# STM32F401RCT6.net
KiCad netlist of a schematic drawn in Altium Designer
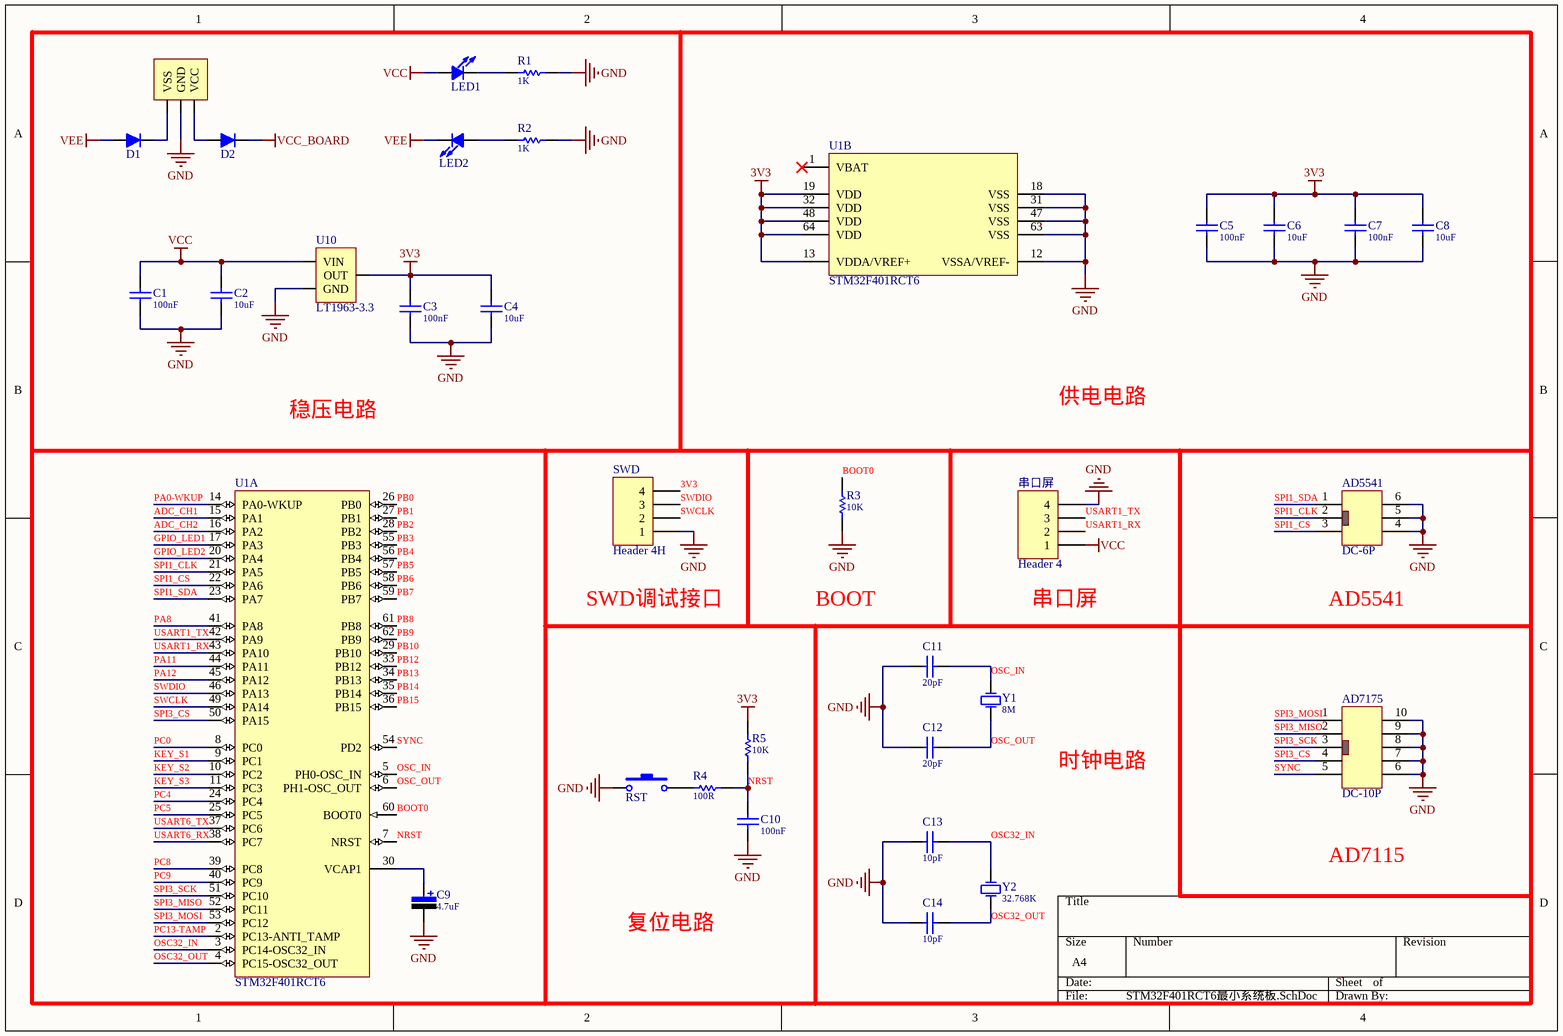
[diagram p0: STM32F401RCT6最小系统板.SchDoc]

(export (version "E")
  (design (tool "Eeschema 10.0.6"))
  (components
    (comp (ref "AD5541") (value "DC-6P") (footprint "DC-6P") (libsource (lib "XuZhe") (part "DC-6P")))
    (comp (ref "AD7175") (value "DC-10P") (footprint "DC-10P") (libsource (lib "XuZhe") (part "DC-10P")))
    (comp (ref "C1")
      (value "100nF")
      (footprint "C0603-L")
      (description "贴片瓷片电容")
      (fields (field (name "Comment") "Cap-S"))
      (libsource (lib "XuZhe") (part "Cap-S"))
    )
    (comp (ref "C2")
      (value "10uF")
      (footprint "C0603-L")
      (description "贴片瓷片电容")
      (fields (field (name "Comment") "Cap-S"))
      (libsource (lib "XuZhe") (part "Cap-S"))
    )
    (comp (ref "C3")
      (value "100nF")
      (footprint "C0603-L")
      (description "贴片瓷片电容")
      (fields (field (name "Comment") "Cap-S"))
      (libsource (lib "XuZhe") (part "Cap-S"))
    )
    (comp (ref "C4")
      (value "10uF")
      (footprint "C0603-L")
      (description "贴片瓷片电容")
      (fields (field (name "Comment") "Cap-S"))
      (libsource (lib "XuZhe") (part "Cap-S"))
    )
    (comp (ref "C5")
      (value "100nF")
      (footprint "C0603-L")
      (description "贴片瓷片电容")
      (fields (field (name "Comment") "Cap-S"))
      (libsource (lib "XuZhe") (part "Cap-S"))
    )
    (comp (ref "C6")
      (value "10uF")
      (footprint "C0603-L")
      (description "贴片瓷片电容")
      (fields (field (name "Comment") "Cap-S"))
      (libsource (lib "XuZhe") (part "Cap-S"))
    )
    (comp (ref "C7")
      (value "100nF")
      (footprint "C0603-L")
      (description "贴片瓷片电容")
      (fields (field (name "Comment") "Cap-S"))
      (libsource (lib "XuZhe") (part "Cap-S"))
    )
    (comp (ref "C8")
      (value "10uF")
      (footprint "C0603-L")
      (description "贴片瓷片电容")
      (fields (field (name "Comment") "Cap-S"))
      (libsource (lib "XuZhe") (part "Cap-S"))
    )
    (comp (ref "C9")
      (value "4.7uF")
      (footprint "C-RB-SD4")
      (description "极性贴片电解电容")
      (fields (field (name "Comment") "C"))
      (libsource (lib "XuZhe") (part "Cap-Pol-ES"))
    )
    (comp (ref "C10")
      (value "100nF")
      (footprint "C0603-L")
      (description "贴片瓷片电容")
      (fields (field (name "Comment") "Cap-S"))
      (libsource (lib "XuZhe") (part "Cap-S"))
    )
    (comp (ref "C11")
      (value "20pF")
      (footprint "C0603-L")
      (description "贴片瓷片电容")
      (fields (field (name "Comment") "Cap-S"))
      (libsource (lib "XuZhe") (part "Cap-S"))
    )
    (comp (ref "C12")
      (value "20pF")
      (footprint "C0603-L")
      (description "贴片瓷片电容")
      (fields (field (name "Comment") "Cap-S"))
      (libsource (lib "XuZhe") (part "Cap-S"))
    )
    (comp (ref "C13")
      (value "10pF")
      (footprint "C0603-L")
      (description "贴片瓷片电容")
      (fields (field (name "Comment") "Cap-S"))
      (libsource (lib "XuZhe") (part "Cap-S"))
    )
    (comp (ref "C14")
      (value "10pF")
      (footprint "C0603-L")
      (description "贴片瓷片电容")
      (fields (field (name "Comment") "Cap-S"))
      (libsource (lib "XuZhe") (part "Cap-S"))
    )
    (comp (ref "D1")
      (value "D")
      (footprint "D-SMA")
      (description "二极管")
      (libsource (lib "XuZhe") (part "Diode"))
    )
    (comp (ref "D2")
      (value "D")
      (footprint "D-SMA")
      (description "二极管")
      (libsource (lib "XuZhe") (part "Diode"))
    )
    (comp (ref "J1")
      (value "Power-3P")
      (footprint "SIPA03")
      (description "供电端子")
      (libsource (lib "XuZhe") (part "Power-3P"))
    )
    (comp (ref "LED1")
      (value "LED")
      (footprint "Led-0805_L")
      (description "发光二极管")
      (libsource (lib "XuZhe") (part "LED"))
    )
    (comp (ref "LED2")
      (value "LED")
      (footprint "Led-0805_L")
      (description "发光二极管")
      (libsource (lib "XuZhe") (part "LED"))
    )
    (comp (ref "R1")
      (value "1K")
      (footprint "R0603-L")
      (description "贴片电阻")
      (fields (field (name "Comment") "R"))
      (libsource (lib "XuZhe") (part "Res"))
    )
    (comp (ref "R2")
      (value "1K")
      (footprint "R0603-L")
      (description "贴片电阻")
      (fields (field (name "Comment") "R"))
      (libsource (lib "XuZhe") (part "Res"))
    )
    (comp (ref "R3")
      (value "10K")
      (footprint "R0603-L")
      (description "贴片电阻")
      (fields (field (name "Comment") "R"))
      (libsource (lib "XuZhe") (part "Res"))
    )
    (comp (ref "R4")
      (value "100R")
      (footprint "R0603-L")
      (description "贴片电阻")
      (fields (field (name "Comment") "R"))
      (libsource (lib "XuZhe") (part "Res"))
    )
    (comp (ref "R5")
      (value "10K")
      (footprint "R0603-L")
      (description "贴片电阻")
      (fields (field (name "Comment") "R"))
      (libsource (lib "XuZhe") (part "Res"))
    )
    (comp (ref "RST")
      (value "SW-PB2")
      (footprint "SW-PB2-SMD")
      (description "贴片式2脚微动开关")
      (libsource (lib "XuZhe") (part "SW-PB2"))
    )
    (comp (ref "SWD")
      (value "Header 4H")
      (footprint "HDR1X4H")
      (description "Header, 4-Pin, Right Angle")
      (fields (field (name "PUBLISHER") "Altium Limited"))
      (libsource (lib "Miscellaneous Connectors") (part "Header 4H"))
    )
    (comp (ref "U1")
      (value "STM32F401RCT6")
      (footprint "STM-LQFP64_L")
      (fields (field (name "MANUFACTURER") "STMicroelectronics"))
      (libsource (lib "STMicroelectronics STM32 F4") (part "STM32F401RCT6"))
    )
    (comp (ref "U10") (value "LT1963-3.3") (footprint "SOT-223") (libsource (lib "XuZhe") (part "AMS1117")))
    (comp (ref "Y1")
      (value "8M")
      (footprint "XTAL-PB2-DIP")
      (description "晶振")
      (fields (field (name "Comment") "XTAL"))
      (libsource (lib "XuZhe") (part "XTAL"))
    )
    (comp (ref "Y2")
      (value "32.768K")
      (footprint "XTAL-32768")
      (description "晶振")
      (fields (field (name "Comment") "XTAL"))
      (libsource (lib "XuZhe") (part "XTAL"))
    )
    (comp (ref "串口屏")
      (value "Header 4")
      (footprint "XH2.54-WI-4P")
      (description "Header, 4-Pin")
      (fields (field (name "PUBLISHER") "Altium Limited"))
      (libsource (lib "Miscellaneous Connectors") (part "Header 4"))
    )
  )
  (nets
    (net (code "1") (name "/ADC_CH1") (class "Default")
      (node (ref "U1") (pin "15") (pinfunction "PA1_15") (pintype "bidirectional"))
    )
    (net (code "2") (name "/ADC_CH2") (class "Default")
      (node (ref "U1") (pin "16") (pinfunction "PA2_16") (pintype "bidirectional"))
    )
    (net (code "3") (name "/BOOT0") (class "Default")
      (node (ref "R3") (pin "2") (pinfunction "2_2") (pintype "passive"))
      (node (ref "U1") (pin "60") (pinfunction "BOOT0_60") (pintype "input"))
    )
    (net (code "4") (name "/GPIO_LED1") (class "Default")
      (node (ref "U1") (pin "17") (pinfunction "PA3_17") (pintype "bidirectional"))
    )
    (net (code "5") (name "/GPIO_LED2") (class "Default")
      (node (ref "U1") (pin "20") (pinfunction "PA4_20") (pintype "bidirectional"))
    )
    (net (code "6") (name "/KEY_S1") (class "Default")
      (node (ref "U1") (pin "9") (pinfunction "PC1_9") (pintype "bidirectional"))
    )
    (net (code "7") (name "/KEY_S2") (class "Default")
      (node (ref "U1") (pin "10") (pinfunction "PC2_10") (pintype "bidirectional"))
    )
    (net (code "8") (name "/KEY_S3") (class "Default")
      (node (ref "U1") (pin "11") (pinfunction "PC3_11") (pintype "bidirectional"))
    )
    (net (code "9") (name "/NRST") (class "Default")
      (node (ref "C10") (pin "2") (pinfunction "2_2") (pintype "passive"))
      (node (ref "R4") (pin "2") (pinfunction "2_2") (pintype "passive"))
      (node (ref "R5") (pin "1") (pinfunction "1_1") (pintype "passive"))
      (node (ref "U1") (pin "7") (pinfunction "NRST_7") (pintype "bidirectional"))
    )
    (net (code "10") (name "/OSC32_IN") (class "Default")
      (node (ref "C13") (pin "2") (pinfunction "2_2") (pintype "passive"))
      (node (ref "U1") (pin "3") (pinfunction "PC14-OSC32_IN_3") (pintype "bidirectional"))
      (node (ref "Y2") (pin "2") (pinfunction "OSC2_2") (pintype "passive"))
    )
    (net (code "11") (name "/OSC32_OUT") (class "Default")
      (node (ref "C14") (pin "2") (pinfunction "2_2") (pintype "passive"))
      (node (ref "U1") (pin "4") (pinfunction "PC15-OSC32_OUT_4") (pintype "bidirectional"))
      (node (ref "Y2") (pin "1") (pinfunction "OSC1_1") (pintype "passive"))
    )
    (net (code "12") (name "/OSC_IN") (class "Default")
      (node (ref "C11") (pin "2") (pinfunction "2_2") (pintype "passive"))
      (node (ref "U1") (pin "5") (pinfunction "PH0-OSC_IN_5") (pintype "bidirectional"))
      (node (ref "Y1") (pin "2") (pinfunction "OSC2_2") (pintype "passive"))
    )
    (net (code "13") (name "/OSC_OUT") (class "Default")
      (node (ref "C12") (pin "2") (pinfunction "2_2") (pintype "passive"))
      (node (ref "U1") (pin "6") (pinfunction "PH1-OSC_OUT_6") (pintype "bidirectional"))
      (node (ref "Y1") (pin "1") (pinfunction "OSC1_1") (pintype "passive"))
    )
    (net (code "14") (name "/PA0-WKUP") (class "Default")
      (node (ref "U1") (pin "14") (pinfunction "PA0-WKUP_14") (pintype "bidirectional"))
    )
    (net (code "15") (name "/PA8") (class "Default")
      (node (ref "U1") (pin "41") (pinfunction "PA8_41") (pintype "bidirectional"))
    )
    (net (code "16") (name "/PA11") (class "Default")
      (node (ref "U1") (pin "44") (pinfunction "PA11_44") (pintype "bidirectional"))
    )
    (net (code "17") (name "/PA12") (class "Default")
      (node (ref "U1") (pin "45") (pinfunction "PA12_45") (pintype "bidirectional"))
    )
    (net (code "18") (name "/PB0") (class "Default")
      (node (ref "U1") (pin "26") (pinfunction "PB0_26") (pintype "bidirectional"))
    )
    (net (code "19") (name "/PB1") (class "Default")
      (node (ref "U1") (pin "27") (pinfunction "PB1_27") (pintype "bidirectional"))
    )
    (net (code "20") (name "/PB2") (class "Default")
      (node (ref "U1") (pin "28") (pinfunction "PB2_28") (pintype "bidirectional"))
    )
    (net (code "21") (name "/PB3") (class "Default")
      (node (ref "U1") (pin "55") (pinfunction "PB3_55") (pintype "bidirectional"))
    )
    (net (code "22") (name "/PB4") (class "Default")
      (node (ref "U1") (pin "56") (pinfunction "PB4_56") (pintype "bidirectional"))
    )
    (net (code "23") (name "/PB5") (class "Default")
      (node (ref "U1") (pin "57") (pinfunction "PB5_57") (pintype "bidirectional"))
    )
    (net (code "24") (name "/PB6") (class "Default")
      (node (ref "U1") (pin "58") (pinfunction "PB6_58") (pintype "bidirectional"))
    )
    (net (code "25") (name "/PB7") (class "Default")
      (node (ref "U1") (pin "59") (pinfunction "PB7_59") (pintype "bidirectional"))
    )
    (net (code "26") (name "/PB8") (class "Default")
      (node (ref "U1") (pin "61") (pinfunction "PB8_61") (pintype "bidirectional"))
    )
    (net (code "27") (name "/PB9") (class "Default")
      (node (ref "U1") (pin "62") (pinfunction "PB9_62") (pintype "bidirectional"))
    )
    (net (code "28") (name "/PB10") (class "Default")
      (node (ref "U1") (pin "29") (pinfunction "PB10_29") (pintype "bidirectional"))
    )
    (net (code "29") (name "/PB12") (class "Default")
      (node (ref "U1") (pin "33") (pinfunction "PB12_33") (pintype "bidirectional"))
    )
    (net (code "30") (name "/PB13") (class "Default")
      (node (ref "U1") (pin "34") (pinfunction "PB13_34") (pintype "bidirectional"))
    )
    (net (code "31") (name "/PB14") (class "Default")
      (node (ref "U1") (pin "35") (pinfunction "PB14_35") (pintype "bidirectional"))
    )
    (net (code "32") (name "/PB15") (class "Default")
      (node (ref "U1") (pin "36") (pinfunction "PB15_36") (pintype "bidirectional"))
    )
    (net (code "33") (name "/PC0") (class "Default")
      (node (ref "U1") (pin "8") (pinfunction "PC0_8") (pintype "bidirectional"))
    )
    (net (code "34") (name "/PC4") (class "Default")
      (node (ref "U1") (pin "24") (pinfunction "PC4_24") (pintype "bidirectional"))
    )
    (net (code "35") (name "/PC5") (class "Default")
      (node (ref "U1") (pin "25") (pinfunction "PC5_25") (pintype "bidirectional"))
    )
    (net (code "36") (name "/PC8") (class "Default")
      (node (ref "U1") (pin "39") (pinfunction "PC8_39") (pintype "bidirectional"))
    )
    (net (code "37") (name "/PC9") (class "Default")
      (node (ref "U1") (pin "40") (pinfunction "PC9_40") (pintype "bidirectional"))
    )
    (net (code "38") (name "/PC13-TAMP") (class "Default")
      (node (ref "U1") (pin "2") (pinfunction "PC13-ANTI_TAMP_2") (pintype "bidirectional"))
    )
    (net (code "39") (name "/SPI1_CLK") (class "Default")
      (node (ref "AD5541") (pin "2") (pinfunction "2_2") (pintype "passive"))
      (node (ref "U1") (pin "21") (pinfunction "PA5_21") (pintype "bidirectional"))
    )
    (net (code "40") (name "/SPI1_CS") (class "Default")
      (node (ref "AD5541") (pin "3") (pinfunction "3_3") (pintype "passive"))
      (node (ref "U1") (pin "22") (pinfunction "PA6_22") (pintype "bidirectional"))
    )
    (net (code "41") (name "/SPI1_SDA") (class "Default")
      (node (ref "AD5541") (pin "1") (pinfunction "1_1") (pintype "passive"))
      (node (ref "U1") (pin "23") (pinfunction "PA7_23") (pintype "bidirectional"))
    )
    (net (code "42") (name "/SPI3_CS") (class "Default")
      (node (ref "AD7175") (pin "4") (pinfunction "4_4") (pintype "passive"))
      (node (ref "U1") (pin "50") (pinfunction "PA15_50") (pintype "bidirectional"))
    )
    (net (code "43") (name "/SPI3_MISO") (class "Default")
      (node (ref "AD7175") (pin "2") (pinfunction "2_2") (pintype "passive"))
      (node (ref "U1") (pin "52") (pinfunction "PC11_52") (pintype "bidirectional"))
    )
    (net (code "44") (name "/SPI3_MOSI") (class "Default")
      (node (ref "AD7175") (pin "1") (pinfunction "1_1") (pintype "passive"))
      (node (ref "U1") (pin "53") (pinfunction "PC12_53") (pintype "bidirectional"))
    )
    (net (code "45") (name "/SPI3_SCK") (class "Default")
      (node (ref "AD7175") (pin "3") (pinfunction "3_3") (pintype "passive"))
      (node (ref "U1") (pin "51") (pinfunction "PC10_51") (pintype "bidirectional"))
    )
    (net (code "46") (name "/SWCLK") (class "Default")
      (node (ref "SWD") (pin "2") (pinfunction "2_2") (pintype "passive"))
      (node (ref "U1") (pin "49") (pinfunction "PA14_49") (pintype "bidirectional"))
    )
    (net (code "47") (name "/SWDIO") (class "Default")
      (node (ref "SWD") (pin "3") (pinfunction "3_3") (pintype "passive"))
      (node (ref "U1") (pin "46") (pinfunction "PA13_46") (pintype "bidirectional"))
    )
    (net (code "48") (name "/SYNC") (class "Default")
      (node (ref "AD7175") (pin "5") (pinfunction "5_5") (pintype "passive"))
      (node (ref "U1") (pin "54") (pinfunction "PD2_54") (pintype "bidirectional"))
    )
    (net (code "49") (name "/USART1_RX") (class "Default")
      (node (ref "U1") (pin "43") (pinfunction "PA10_43") (pintype "bidirectional"))
      (node (ref "串口屏") (pin "2") (pinfunction "2_2") (pintype "passive"))
    )
    (net (code "50") (name "/USART1_TX") (class "Default")
      (node (ref "U1") (pin "42") (pinfunction "PA9_42") (pintype "bidirectional"))
      (node (ref "串口屏") (pin "3") (pinfunction "3_3") (pintype "passive"))
    )
    (net (code "51") (name "/USART6_RX") (class "Default")
      (node (ref "U1") (pin "38") (pinfunction "PC7_38") (pintype "bidirectional"))
    )
    (net (code "52") (name "/USART6_TX") (class "Default")
      (node (ref "U1") (pin "37") (pinfunction "PC6_37") (pintype "bidirectional"))
    )
    (net (code "53") (name "3V3") (class "Default")
      (node (ref "C3") (pin "2") (pinfunction "2_2") (pintype "passive"))
      (node (ref "C4") (pin "2") (pinfunction "2_2") (pintype "passive"))
      (node (ref "C5") (pin "2") (pinfunction "2_2") (pintype "passive"))
      (node (ref "C6") (pin "2") (pinfunction "2_2") (pintype "passive"))
      (node (ref "C7") (pin "2") (pinfunction "2_2") (pintype "passive"))
      (node (ref "C8") (pin "2") (pinfunction "2_2") (pintype "passive"))
      (node (ref "R5") (pin "2") (pinfunction "2_2") (pintype "passive"))
      (node (ref "SWD") (pin "4") (pinfunction "4_4") (pintype "passive"))
      (node (ref "U1") (pin "13") (pinfunction "VDDA/VREF+_13") (pintype "power_in"))
      (node (ref "U1") (pin "19") (pinfunction "VDD_19") (pintype "power_in"))
      (node (ref "U1") (pin "32") (pinfunction "VDD_32") (pintype "power_in"))
      (node (ref "U1") (pin "48") (pinfunction "VDD_48") (pintype "power_in"))
      (node (ref "U1") (pin "64") (pinfunction "VDD_64") (pintype "power_in"))
      (node (ref "U10") (pin "2") (pinfunction "OUT_2") (pintype "passive"))
    )
    (net (code "54") (name "GND") (class "Default")
      (node (ref "AD5541") (pin "4") (pinfunction "4_4") (pintype "passive"))
      (node (ref "AD5541") (pin "5") (pinfunction "5_5") (pintype "passive"))
      (node (ref "AD5541") (pin "6") (pinfunction "6_6") (pintype "passive"))
      (node (ref "AD7175") (pin "10") (pinfunction "10_10") (pintype "passive"))
      (node (ref "AD7175") (pin "6") (pinfunction "6_6") (pintype "passive"))
      (node (ref "AD7175") (pin "7") (pinfunction "7_7") (pintype "passive"))
      (node (ref "AD7175") (pin "8") (pinfunction "8_8") (pintype "passive"))
      (node (ref "AD7175") (pin "9") (pinfunction "9_9") (pintype "passive"))
      (node (ref "C1") (pin "1") (pinfunction "1_1") (pintype "passive"))
      (node (ref "C10") (pin "1") (pinfunction "1_1") (pintype "passive"))
      (node (ref "C11") (pin "1") (pinfunction "1_1") (pintype "passive"))
      (node (ref "C12") (pin "1") (pinfunction "1_1") (pintype "passive"))
      (node (ref "C13") (pin "1") (pinfunction "1_1") (pintype "passive"))
      (node (ref "C14") (pin "1") (pinfunction "1_1") (pintype "passive"))
      (node (ref "C2") (pin "1") (pinfunction "1_1") (pintype "passive"))
      (node (ref "C3") (pin "1") (pinfunction "1_1") (pintype "passive"))
      (node (ref "C4") (pin "1") (pinfunction "1_1") (pintype "passive"))
      (node (ref "C5") (pin "1") (pinfunction "1_1") (pintype "passive"))
      (node (ref "C6") (pin "1") (pinfunction "1_1") (pintype "passive"))
      (node (ref "C7") (pin "1") (pinfunction "1_1") (pintype "passive"))
      (node (ref "C8") (pin "1") (pinfunction "1_1") (pintype "passive"))
      (node (ref "C9") (pin "2") (pinfunction "2_2") (pintype "passive"))
      (node (ref "J1") (pin "2") (pinfunction "GND_2") (pintype "passive"))
      (node (ref "R1") (pin "2") (pinfunction "2_2") (pintype "passive"))
      (node (ref "R2") (pin "2") (pinfunction "2_2") (pintype "passive"))
      (node (ref "R3") (pin "1") (pinfunction "1_1") (pintype "passive"))
      (node (ref "RST") (pin "1") (pinfunction "1_1") (pintype "passive"))
      (node (ref "SWD") (pin "1") (pinfunction "1_1") (pintype "passive"))
      (node (ref "U1") (pin "12") (pinfunction "VSSA/VREF-_12") (pintype "power_in"))
      (node (ref "U1") (pin "18") (pinfunction "VSS_18") (pintype "power_in"))
      (node (ref "U1") (pin "31") (pinfunction "VSS_31") (pintype "power_in"))
      (node (ref "U1") (pin "47") (pinfunction "VSS_47") (pintype "power_in"))
      (node (ref "U1") (pin "63") (pinfunction "VSS_63") (pintype "power_in"))
      (node (ref "U10") (pin "1") (pinfunction "GND_1") (pintype "passive"))
      (node (ref "串口屏") (pin "4") (pinfunction "4_4") (pintype "passive"))
    )
    (net (code "55") (name "Net-(J1-VCC)") (class "Default")
      (node (ref "D2") (pin "1") (pinfunction "1_1") (pintype "passive"))
      (node (ref "J1") (pin "1") (pinfunction "VCC_1") (pintype "passive"))
    )
    (net (code "56") (name "Net-(J1-VSS)") (class "Default")
      (node (ref "D1") (pin "2") (pinfunction "2_2") (pintype "passive"))
      (node (ref "J1") (pin "3") (pinfunction "VSS_3") (pintype "passive"))
    )
    (net (code "57") (name "Net-(LED1-Pad2)") (class "Default")
      (node (ref "LED1") (pin "2") (pinfunction "2_2") (pintype "passive"))
      (node (ref "R1") (pin "1") (pinfunction "1_1") (pintype "passive"))
    )
    (net (code "58") (name "Net-(LED2-Pad1)") (class "Default")
      (node (ref "LED2") (pin "1") (pinfunction "1_1") (pintype "passive"))
      (node (ref "R2") (pin "1") (pinfunction "1_1") (pintype "passive"))
    )
    (net (code "59") (name "Net-(R4-Pad1)") (class "Default")
      (node (ref "R4") (pin "1") (pinfunction "1_1") (pintype "passive"))
      (node (ref "RST") (pin "2") (pinfunction "2_2") (pintype "passive"))
    )
    (net (code "60") (name "Net-(U1A-VCAP1)") (class "Default")
      (node (ref "C9") (pin "1") (pinfunction "1_1") (pintype "passive"))
      (node (ref "U1") (pin "30") (pinfunction "VCAP1_30") (pintype "power_in"))
    )
    (net (code "61") (name "VCC") (class "Default")
      (node (ref "C1") (pin "2") (pinfunction "2_2") (pintype "passive"))
      (node (ref "C2") (pin "2") (pinfunction "2_2") (pintype "passive"))
      (node (ref "LED1") (pin "1") (pinfunction "1_1") (pintype "passive"))
      (node (ref "U10") (pin "3") (pinfunction "VIN_3") (pintype "passive"))
      (node (ref "串口屏") (pin "1") (pinfunction "1_1") (pintype "passive"))
    )
    (net (code "62") (name "VCC_BOARD") (class "Default")
      (node (ref "D2") (pin "2") (pinfunction "2_2") (pintype "passive"))
    )
    (net (code "63") (name "VEE") (class "Default")
      (node (ref "D1") (pin "1") (pinfunction "1_1") (pintype "passive"))
      (node (ref "LED2") (pin "2") (pinfunction "2_2") (pintype "passive"))
    )
    (net (code "64") (name "unconnected-(U1B-VBAT-Pad1)") (class "Default")
      (node (ref "U1") (pin "1") (pinfunction "VBAT_1") (pintype "power_in+no_connect"))
    )
  )
)
